# CAPACITOR_CHARGER.net
KiCad netlist of a schematic drawn in Altium Designer
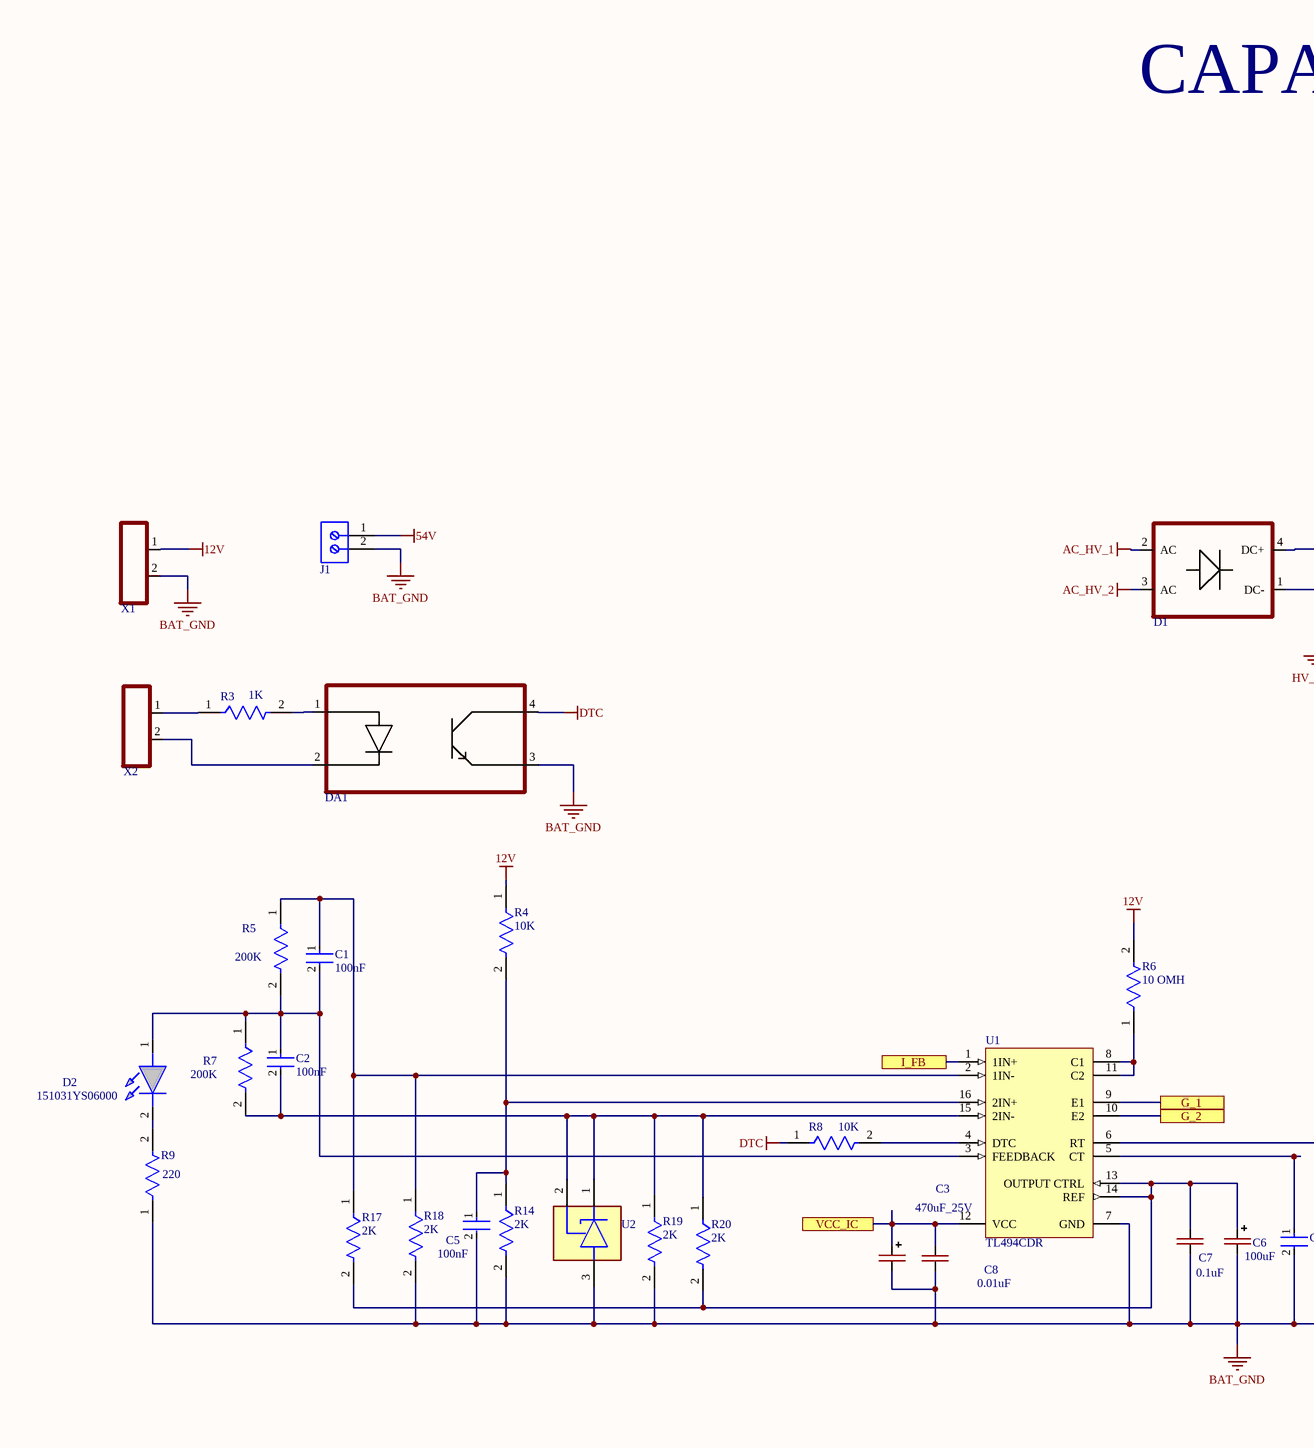
[diagram p0: CAPACITOR_CHARGER.SchDoc, left]
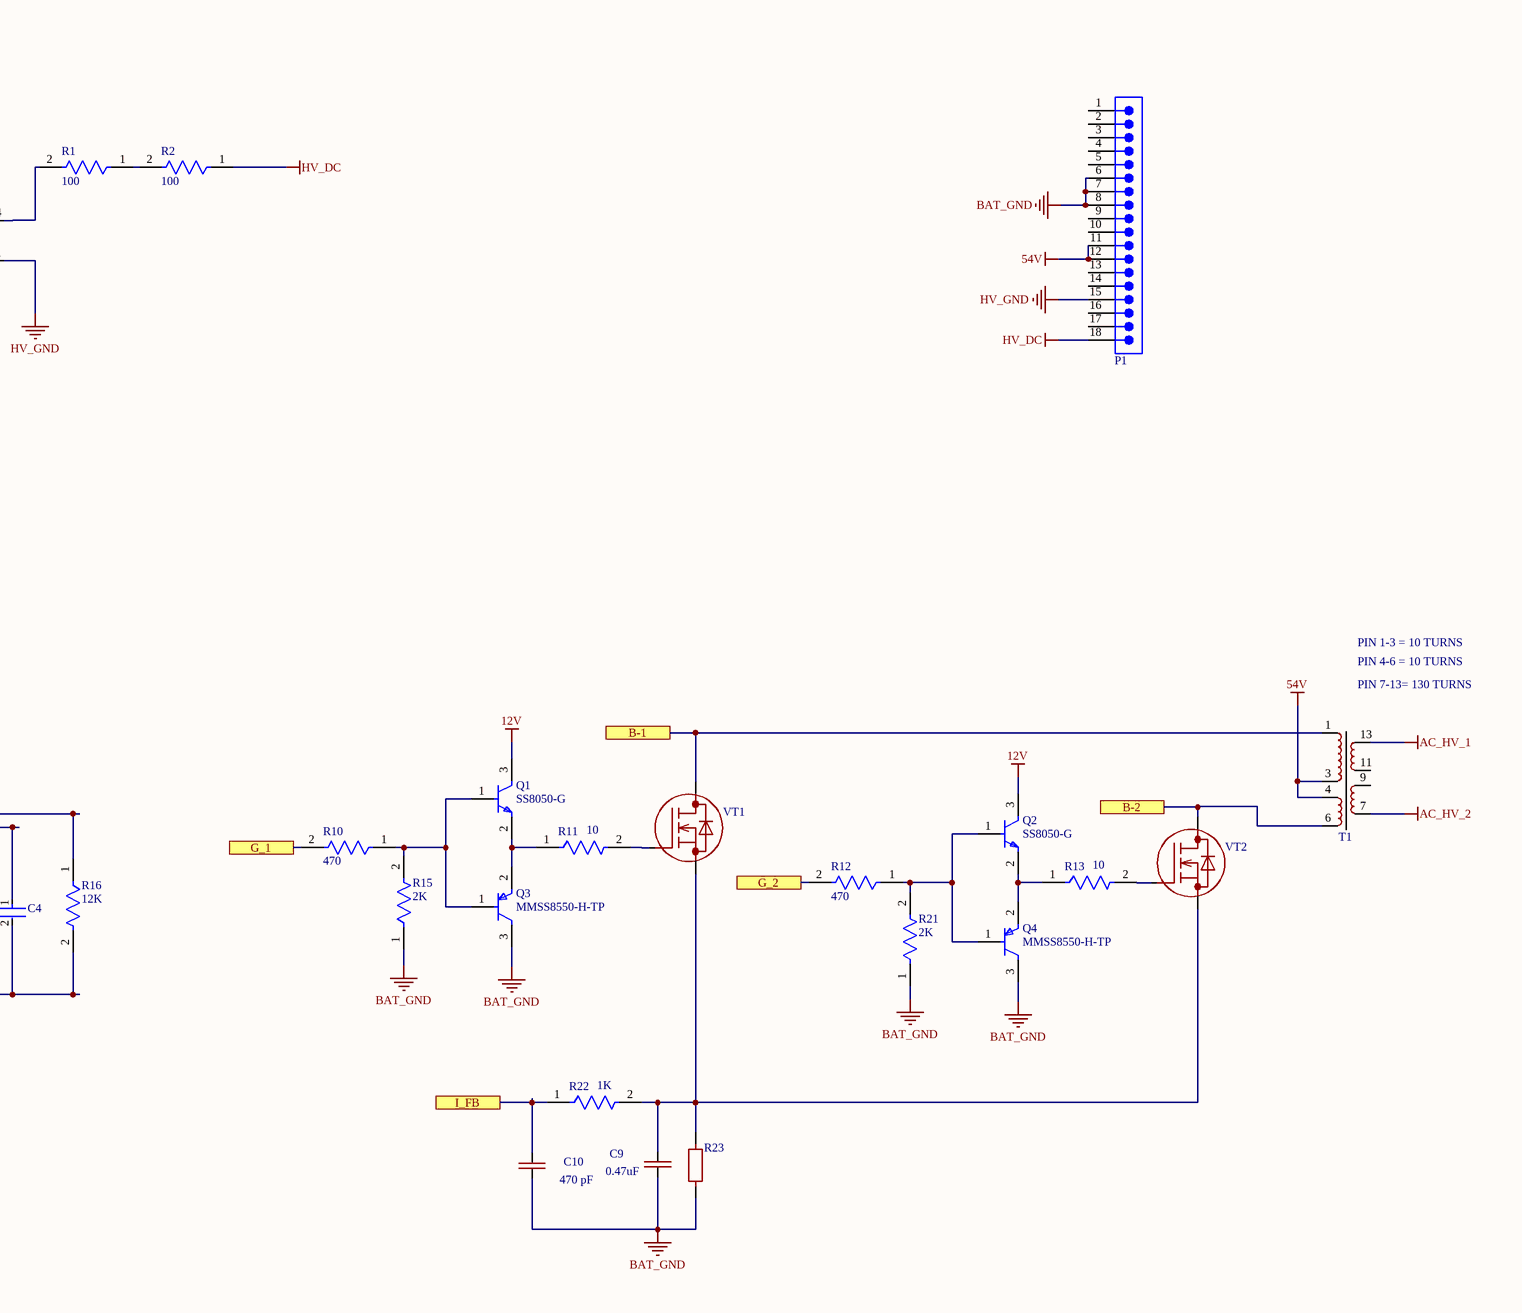
[diagram p1: CAPACITOR_CHARGER.SchDoc, right]

(export (version "E")
  (design (tool "Eeschema 10.0.6"))
  (components
    (comp (ref "C1")
      (value "100nF")
      (footprint "FP-C0805C-DN-MFG")
      (description "CAP CER 10000PF 50V X7R 0805")
      (fields
        (field (name "MANUFACTURER PART NUMBER") "C0805C103J5RACTU")
        (field (name "MANUFACTURER") "KEMET")
      )
      (libsource (lib "Altium Content Vault") (part "b4654b650e69147ec39a6b967a45e02"))
    )
    (comp (ref "C2")
      (value "100nF")
      (footprint "FP-C0805C-DN-MFG")
      (description "CAP CER 10000PF 50V X7R 0805")
      (fields
        (field (name "MANUFACTURER PART NUMBER") "C0805C103J5RACTU")
        (field (name "MANUFACTURER") "KEMET")
      )
      (libsource (lib "Altium Content Vault") (part "b4654b650e69147ec39a6b967a45e02"))
    )
    (comp (ref "C3")
      (value "470uF_25V")
      (footprint "CAP_SMD_Size_G")
      (libsource (lib "PASSIVE_COMPONENTS") (part "CAP-POLAR"))
    )
    (comp (ref "C4")
      (value "C0805C102K5RACTU")
      (footprint "FP-C0805C-DN-MFG")
      (description "CAP CER 1000PF 50V X7R 0805")
      (fields
        (field (name "OCTOPART") "https://octopart.com/c0805c102k5ractu-kemet-93010")
        (field (name "TOLERANCE") "0.1")
      )
      (libsource (lib "Altium Content Vault") (part "b4654b650e69147ec39a6b967a45e02"))
    )
    (comp (ref "C5")
      (value "100nF")
      (footprint "FP-C0805C-DN-MFG")
      (description "CAP CER 10000PF 50V X7R 0805")
      (fields
        (field (name "MANUFACTURER PART NUMBER") "C0805C103J5RACTU")
        (field (name "MANUFACTURER") "KEMET")
      )
      (libsource (lib "Altium Content Vault") (part "b4654b650e69147ec39a6b967a45e02"))
    )
    (comp (ref "C6")
      (value "100uF")
      (footprint "CAP-TAN-D")
      (libsource (lib "PASSIVE_COMPONENTS") (part "CAP-POLAR"))
    )
    (comp (ref "C7")
      (value "0.1uF")
      (footprint "CAP-0805")
      (libsource (lib "PASSIVE_COMPONENTS") (part "CAP-NON-POLAR"))
    )
    (comp (ref "C8")
      (value "0.01uF")
      (footprint "CAP-0805")
      (libsource (lib "PASSIVE_COMPONENTS") (part "CAP-NON-POLAR"))
    )
    (comp (ref "C9")
      (value "0.47uF")
      (footprint "CAP-0805")
      (libsource (lib "PASSIVE_COMPONENTS") (part "CAP-NON-POLAR"))
    )
    (comp (ref "C10")
      (value "470 pF")
      (footprint "CAP-0805")
      (libsource (lib "PASSIVE_COMPONENTS") (part "CAP-NON-POLAR"))
    )
    (comp (ref "D1") (value "RS40X") (footprint "RS40X") (libsource (lib "RS40X") (part "RS40X")))
    (comp (ref "D2")
      (value "151031YS06000")
      (footprint "LED_RED")
      (description "WURTH ELEKTRONIK - 151031YS06000 - LED, Yellow, Through Hole, T-1 (3mm), 30 mA, 2 V, 590 nm")
      (fields (field (name "MOUSER PART NUMBER") "710-151031YS06000"))
      (libsource (lib "Optic-LED") (part "LED"))
    )
    (comp (ref "DA1") (value "PC817") (footprint "4-SMD") (libsource (lib "PC817") (part "PC817")))
    (comp (ref "J1")
      (value "691101710002")
      (footprint "691101710002")
      (description "WR-TBL Series 101 Horizontal Entry Modular, THT, pitch 5mm, 2p")
      (fields (field (name "MANUFACTURER") "Wurth Elektronik"))
      (libsource (lib "Altium_WR-TBL (rev22b)") (part "691101710002"))
    )
    (comp (ref "P1")
      (value "61301811021")
      (footprint "61301811021")
      (description "WR-PHD Pin Header, THT, Angled, pitch 2.54mm, 1 Row, 18P")
      (fields (field (name "MANUFACTURER") "Wurth Elektronik"))
      (libsource (lib "Altium_WR-PHD (rev22b)") (part "61301811021"))
    )
    (comp (ref "Q1")
      (value "SS8050-G")
      (footprint "FP-SS8050-G-MFG")
      (description "NPN TRANSISTOR 1.5A 40V SOT-23 R")
      (libsource (lib "Altium Content Vault") (part "2a1388f82443b098dcd57d24ac7632d"))
    )
    (comp (ref "Q2")
      (value "SS8050-G")
      (footprint "FP-SS8050-G-MFG")
      (description "NPN TRANSISTOR 1.5A 40V SOT-23 R")
      (libsource (lib "Altium Content Vault") (part "2a1388f82443b098dcd57d24ac7632d"))
    )
    (comp (ref "Q3")
      (value "MMSS8550-H-TP")
      (footprint "FP-SOT-23-IPC_B")
      (description "TRANS PNP 25V 1.5A SOT23")
      (libsource (lib "Altium Content Vault") (part "0e8486ed3b47d9c69b8404ba87cf0f7"))
    )
    (comp (ref "Q4")
      (value "MMSS8550-H-TP")
      (footprint "FP-SOT-23-IPC_B")
      (description "TRANS PNP 25V 1.5A SOT23")
      (libsource (lib "Altium Content Vault") (part "0e8486ed3b47d9c69b8404ba87cf0f7"))
    )
    (comp (ref "R1")
      (value "100")
      (footprint "RES-2W")
      (libsource (lib "PASSIVE_COMPONENTS") (part "RES-CONST"))
    )
    (comp (ref "R2")
      (value "100")
      (footprint "RES-2W")
      (libsource (lib "PASSIVE_COMPONENTS") (part "RES-CONST"))
    )
    (comp (ref "R3")
      (value "1K")
      (footprint "RES-0805")
      (libsource (lib "PASSIVE_COMPONENTS") (part "RES-CONST"))
    )
    (comp (ref "R4")
      (value "10K")
      (footprint "FP-CRCW0805-e3-MFG")
      (description "RES Thick Film, 2kΩ, 1%, 0.125W, 100ppm/°C, 0805")
      (fields (field (name "TOLERANCE") "1%"))
      (libsource (lib "Pasive_components") (part "CMP-2001-04908-2"))
    )
    (comp (ref "R5")
      (value "200K")
      (footprint "FP-CRCW0805-e3-MFG")
      (description "RES Thick Film, 2kΩ, 1%, 0.125W, 100ppm/°C, 0805")
      (fields (field (name "TOLERANCE") "1%"))
      (libsource (lib "Pasive_components") (part "CMP-2001-04908-2"))
    )
    (comp (ref "R6")
      (value "10 OMH")
      (footprint "RES-1206")
      (libsource (lib "PASSIVE_COMPONENTS") (part "RES-CONST"))
    )
    (comp (ref "R7")
      (value "200K")
      (footprint "FP-CRCW0805-e3-MFG")
      (description "RES Thick Film, 2kΩ, 1%, 0.125W, 100ppm/°C, 0805")
      (fields (field (name "TOLERANCE") "1%"))
      (libsource (lib "Pasive_components") (part "CMP-2001-04908-2"))
    )
    (comp (ref "R8")
      (value "10K")
      (footprint "RES-0805")
      (libsource (lib "PASSIVE_COMPONENTS") (part "RES-CONST"))
    )
    (comp (ref "R9")
      (value "220")
      (footprint "RES-0805")
      (libsource (lib "PASSIVE_COMPONENTS") (part "RES-CONST"))
    )
    (comp (ref "R10")
      (value "470")
      (footprint "RES-0805")
      (libsource (lib "PASSIVE_COMPONENTS") (part "RES-CONST"))
    )
    (comp (ref "R11")
      (value "10")
      (footprint "RES-0805")
      (libsource (lib "PASSIVE_COMPONENTS") (part "RES-CONST"))
    )
    (comp (ref "R12")
      (value "470")
      (footprint "RES-0805")
      (libsource (lib "PASSIVE_COMPONENTS") (part "RES-CONST"))
    )
    (comp (ref "R13")
      (value "10")
      (footprint "RES-0805")
      (libsource (lib "PASSIVE_COMPONENTS") (part "RES-CONST"))
    )
    (comp (ref "R14")
      (value "2K")
      (footprint "FP-CRCW0805-e3-MFG")
      (description "RES Thick Film, 2kΩ, 1%, 0.125W, 100ppm/°C, 0805")
      (fields (field (name "TOLERANCE") "1%"))
      (libsource (lib "Pasive_components") (part "CMP-2001-04908-2"))
    )
    (comp (ref "R15")
      (value "2K")
      (footprint "RES-0805")
      (libsource (lib "PASSIVE_COMPONENTS") (part "RES-CONST"))
    )
    (comp (ref "R16")
      (value "12K")
      (footprint "FP-CRCW0805-e3-MFG")
      (description "RES Thick Film, 12kΩ, 1%, 0.125W, 100ppm/°C, 0805")
      (fields (field (name "TOLERANCE") "1%"))
      (libsource (lib "Pasive_components") (part "CMP-2001-04908-2"))
    )
    (comp (ref "R17")
      (value "2K")
      (footprint "FP-CRCW0805-e3-MFG")
      (description "RES Thick Film, 2kΩ, 1%, 0.125W, 100ppm/°C, 0805")
      (fields (field (name "TOLERANCE") "1%"))
      (libsource (lib "Pasive_components") (part "CMP-2001-04908-2"))
    )
    (comp (ref "R18")
      (value "2K")
      (footprint "FP-CRCW0805-e3-MFG")
      (description "RES Thick Film, 82kΩ, 1%, 0.125W, 100ppm/°C, 0805")
      (fields (field (name "TOLERANCE") "1%"))
      (libsource (lib "Pasive_components") (part "CMP-2001-04908-2"))
    )
    (comp (ref "R19")
      (value "2K")
      (footprint "FP-CRCW0805-e3-MFG")
      (description "RES Thick Film, 2kΩ, 1%, 0.125W, 100ppm/°C, 0805")
      (fields (field (name "TOLERANCE") "1%"))
      (libsource (lib "Pasive_components") (part "CMP-2001-04908-2"))
    )
    (comp (ref "R20")
      (value "2K")
      (footprint "FP-CRCW0805-e3-MFG")
      (description "RES Thick Film, 2kΩ, 1%, 0.125W, 100ppm/°C, 0805")
      (fields (field (name "TOLERANCE") "1%"))
      (libsource (lib "Pasive_components") (part "CMP-2001-04908-2"))
    )
    (comp (ref "R21")
      (value "2K")
      (footprint "RES-0805")
      (libsource (lib "PASSIVE_COMPONENTS") (part "RES-CONST"))
    )
    (comp (ref "R22")
      (value "1K")
      (footprint "RES-0805")
      (libsource (lib "PASSIVE_COMPONENTS") (part "RES-CONST"))
    )
    (comp (ref "R23") (value "~") (footprint "RES-2W") (libsource (lib "PAS_COMPONENTS") (part "RES-CONST")))
    (comp (ref "T1")
      (value "ETD29")
      (footprint "TRANS_ETD_29")
      (libsource (lib "ETD_29") (part "Trans_ETD59"))
    )
    (comp (ref "U1")
      (value "TL494CDR")
      (footprint "D0016A_N")
      (fields (field (name "MANUFACTURER") "Texas Instruments"))
      (libsource (lib "Altium Content Vault") (part "TI-494D16"))
    )
    (comp (ref "U2")
      (value "TL431")
      (footprint "TL431_SOT-23-3(A)")
      (description "TL431_SOT-23-3")
      (libsource (lib "Diodes") (part "TL431_SOT-23-3"))
    )
    (comp (ref "VT1")
      (value "MOSFET-N-GDS")
      (footprint "TO-220-3")
      (libsource (lib "TRANSISTORS") (part "MOSFET-N-GDS"))
    )
    (comp (ref "VT2")
      (value "MOSFET-N-GDS")
      (footprint "TO-220-3")
      (libsource (lib "TRANSISTORS") (part "MOSFET-N-GDS"))
    )
    (comp (ref "X1") (value "CONN-2-PIN") (footprint "XH2-") (libsource (lib "XH 2PIN") (part "CONN-2-PIN")))
    (comp (ref "X2") (value "CONN-2-PIN") (footprint "XH2-") (libsource (lib "XH 2PIN") (part "CONN-2-PIN")))
  )
  (nets
    (net (code "1") (name "/B-1") (class "Default")
      (node (ref "T1") (pin "1") (pinfunction "1_1") (pintype "passive"))
      (node (ref "VT1") (pin "2") (pinfunction "D_2") (pintype "passive"))
    )
    (net (code "2") (name "/B-2") (class "Default")
      (node (ref "T1") (pin "6") (pinfunction "6_6") (pintype "passive"))
      (node (ref "VT2") (pin "2") (pinfunction "D_2") (pintype "passive"))
    )
    (net (code "3") (name "/G_1") (class "Default")
      (node (ref "R10") (pin "2") (pinfunction "2_2") (pintype "passive"))
      (node (ref "U1") (pin "9") (pinfunction "E1_9") (pintype "passive"))
    )
    (net (code "4") (name "/G_2") (class "Default")
      (node (ref "R12") (pin "2") (pinfunction "2_2") (pintype "passive"))
      (node (ref "U1") (pin "10") (pinfunction "E2_10") (pintype "passive"))
    )
    (net (code "5") (name "/I_FB") (class "Default")
      (node (ref "C10") (pin "2") (pinfunction "2_2") (pintype "passive"))
      (node (ref "R22") (pin "1") (pinfunction "1_1") (pintype "passive"))
      (node (ref "U1") (pin "1") (pinfunction "1IN+_1") (pintype "input"))
    )
    (net (code "6") (name "/VCC_IC") (class "Default")
      (node (ref "C3") (pin "1") (pinfunction "+_1") (pintype "passive"))
      (node (ref "C8") (pin "2") (pinfunction "2_2") (pintype "passive"))
      (node (ref "U1") (pin "12") (pinfunction "VCC_12") (pintype "power_in"))
    )
    (net (code "7") (name "12V") (class "Default")
      (node (ref "Q1") (pin "3") (pinfunction "C_3") (pintype "passive"))
      (node (ref "Q2") (pin "3") (pinfunction "C_3") (pintype "passive"))
      (node (ref "R4") (pin "1") (pinfunction "1_1") (pintype "passive"))
      (node (ref "R6") (pin "2") (pinfunction "2_2") (pintype "passive"))
      (node (ref "X1") (pin "1") (pinfunction "1_1") (pintype "passive"))
    )
    (net (code "8") (name "54V") (class "Default")
      (node (ref "J1") (pin "1") (pinfunction "1_1") (pintype "passive"))
      (node (ref "P1") (pin "11") (pinfunction "11_11") (pintype "passive"))
      (node (ref "P1") (pin "12") (pinfunction "12_12") (pintype "passive"))
      (node (ref "T1") (pin "3") (pinfunction "3_3") (pintype "passive"))
      (node (ref "T1") (pin "4") (pinfunction "4_4") (pintype "passive"))
    )
    (net (code "9") (name "AC_HV_1") (class "Default")
      (node (ref "D1") (pin "2") (pinfunction "AC_2") (pintype "passive"))
      (node (ref "T1") (pin "13") (pinfunction "13_13") (pintype "passive"))
    )
    (net (code "10") (name "AC_HV_2") (class "Default")
      (node (ref "D1") (pin "3") (pinfunction "AC_3") (pintype "passive"))
      (node (ref "T1") (pin "7") (pinfunction "7_7") (pintype "passive"))
    )
    (net (code "11") (name "BAT_GND") (class "Default")
      (node (ref "C10") (pin "1") (pinfunction "1_1") (pintype "passive"))
      (node (ref "C3") (pin "2") (pinfunction "-_2") (pintype "passive"))
      (node (ref "C4") (pin "2") (pinfunction "2_2") (pintype "passive"))
      (node (ref "C5") (pin "2") (pinfunction "2_2") (pintype "passive"))
      (node (ref "C6") (pin "2") (pinfunction "-_2") (pintype "passive"))
      (node (ref "C7") (pin "1") (pinfunction "1_1") (pintype "passive"))
      (node (ref "C8") (pin "1") (pinfunction "1_1") (pintype "passive"))
      (node (ref "C9") (pin "1") (pinfunction "1_1") (pintype "passive"))
      (node (ref "DA1") (pin "3") (pinfunction "EMITTER_3") (pintype "passive"))
      (node (ref "J1") (pin "2") (pinfunction "2_2") (pintype "passive"))
      (node (ref "P1") (pin "6") (pinfunction "6_6") (pintype "passive"))
      (node (ref "P1") (pin "7") (pinfunction "7_7") (pintype "passive"))
      (node (ref "P1") (pin "8") (pinfunction "8_8") (pintype "passive"))
      (node (ref "Q3") (pin "3") (pinfunction "C_3") (pintype "passive"))
      (node (ref "Q4") (pin "3") (pinfunction "C_3") (pintype "passive"))
      (node (ref "R14") (pin "2") (pinfunction "2_2") (pintype "passive"))
      (node (ref "R15") (pin "1") (pinfunction "1_1") (pintype "passive"))
      (node (ref "R16") (pin "2") (pinfunction "2_2") (pintype "passive"))
      (node (ref "R18") (pin "2") (pinfunction "2_2") (pintype "passive"))
      (node (ref "R19") (pin "2") (pinfunction "2_2") (pintype "passive"))
      (node (ref "R21") (pin "1") (pinfunction "1_1") (pintype "passive"))
      (node (ref "R23") (pin "1") (pinfunction "1_1") (pintype "passive"))
      (node (ref "R9") (pin "1") (pinfunction "1_1") (pintype "passive"))
      (node (ref "U1") (pin "7") (pinfunction "GND_7") (pintype "power_in"))
      (node (ref "U2") (pin "3") (pinfunction "A_3") (pintype "passive"))
      (node (ref "X1") (pin "2") (pinfunction "2_2") (pintype "passive"))
    )
    (net (code "12") (name "DTC") (class "Default")
      (node (ref "DA1") (pin "4") (pinfunction "COLLECTOR_4") (pintype "passive"))
      (node (ref "R8") (pin "1") (pinfunction "1_1") (pintype "passive"))
    )
    (net (code "13") (name "HV_DC") (class "Default")
      (node (ref "P1") (pin "18") (pinfunction "18_18") (pintype "passive"))
      (node (ref "R2") (pin "1") (pinfunction "1_1") (pintype "passive"))
    )
    (net (code "14") (name "HV_GND") (class "Default")
      (node (ref "D1") (pin "1") (pinfunction "DC-_1") (pintype "passive"))
      (node (ref "P1") (pin "15") (pinfunction "15_15") (pintype "passive"))
    )
    (net (code "15") (name "Net-(C6-+)") (class "Default")
      (node (ref "C6") (pin "1") (pinfunction "+_1") (pintype "passive"))
      (node (ref "C7") (pin "2") (pinfunction "2_2") (pintype "passive"))
      (node (ref "R17") (pin "2") (pinfunction "2_2") (pintype "passive"))
      (node (ref "R20") (pin "2") (pinfunction "2_2") (pintype "passive"))
      (node (ref "U1") (pin "13") (pinfunction "OUTPUT_CTRL_13") (pintype "input"))
      (node (ref "U1") (pin "14") (pinfunction "REF_14") (pintype "output"))
    )
    (net (code "16") (name "Net-(D1-DC+)") (class "Default")
      (node (ref "D1") (pin "4") (pinfunction "DC+_4") (pintype "passive"))
      (node (ref "R1") (pin "2") (pinfunction "2_2") (pintype "passive"))
    )
    (net (code "17") (name "Net-(D2-A)") (class "Default")
      (node (ref "C1") (pin "2") (pinfunction "2_2") (pintype "passive"))
      (node (ref "C2") (pin "1") (pinfunction "1_1") (pintype "passive"))
      (node (ref "D2") (pin "1") (pinfunction "A_1") (pintype "passive"))
      (node (ref "R5") (pin "2") (pinfunction "2_2") (pintype "passive"))
      (node (ref "R7") (pin "1") (pinfunction "1_1") (pintype "passive"))
      (node (ref "U1") (pin "3") (pinfunction "FEEDBACK_3") (pintype "input"))
    )
    (net (code "18") (name "Net-(D2-K)") (class "Default")
      (node (ref "D2") (pin "2") (pinfunction "K_2") (pintype "passive"))
      (node (ref "R9") (pin "2") (pinfunction "2_2") (pintype "passive"))
    )
    (net (code "19") (name "Net-(DA1-ANODE)") (class "Default")
      (node (ref "DA1") (pin "1") (pinfunction "ANODE_1") (pintype "passive"))
      (node (ref "R3") (pin "2") (pinfunction "2_2") (pintype "passive"))
    )
    (net (code "20") (name "Net-(DA1-CATHODE)") (class "Default")
      (node (ref "DA1") (pin "2") (pinfunction "CATHODE_2") (pintype "passive"))
      (node (ref "X2") (pin "2") (pinfunction "2_2") (pintype "passive"))
    )
    (net (code "21") (name "Net-(Q1-B)") (class "Default")
      (node (ref "Q1") (pin "1") (pinfunction "B_1") (pintype "passive"))
      (node (ref "Q3") (pin "1") (pinfunction "B_1") (pintype "passive"))
      (node (ref "R10") (pin "1") (pinfunction "1_1") (pintype "passive"))
      (node (ref "R15") (pin "2") (pinfunction "2_2") (pintype "passive"))
    )
    (net (code "22") (name "Net-(Q1-E)") (class "Default")
      (node (ref "Q1") (pin "2") (pinfunction "E_2") (pintype "passive"))
      (node (ref "Q3") (pin "2") (pinfunction "E_2") (pintype "passive"))
      (node (ref "R11") (pin "1") (pinfunction "1_1") (pintype "passive"))
    )
    (net (code "23") (name "Net-(Q2-B)") (class "Default")
      (node (ref "Q2") (pin "1") (pinfunction "B_1") (pintype "passive"))
      (node (ref "Q4") (pin "1") (pinfunction "B_1") (pintype "passive"))
      (node (ref "R12") (pin "1") (pinfunction "1_1") (pintype "passive"))
      (node (ref "R21") (pin "2") (pinfunction "2_2") (pintype "passive"))
    )
    (net (code "24") (name "Net-(Q2-E)") (class "Default")
      (node (ref "Q2") (pin "2") (pinfunction "E_2") (pintype "passive"))
      (node (ref "Q4") (pin "2") (pinfunction "E_2") (pintype "passive"))
      (node (ref "R13") (pin "1") (pinfunction "1_1") (pintype "passive"))
    )
    (net (code "25") (name "Net-(R1-Pad1)") (class "Default")
      (node (ref "R1") (pin "1") (pinfunction "1_1") (pintype "passive"))
      (node (ref "R2") (pin "2") (pinfunction "2_2") (pintype "passive"))
    )
    (net (code "26") (name "Net-(R3-Pad1)") (class "Default")
      (node (ref "R3") (pin "1") (pinfunction "1_1") (pintype "passive"))
      (node (ref "X2") (pin "1") (pinfunction "1_1") (pintype "passive"))
    )
    (net (code "27") (name "Net-(U1-1IN-)") (class "Default")
      (node (ref "C1") (pin "1") (pinfunction "1_1") (pintype "passive"))
      (node (ref "R17") (pin "1") (pinfunction "1_1") (pintype "passive"))
      (node (ref "R18") (pin "1") (pinfunction "1_1") (pintype "passive"))
      (node (ref "R5") (pin "1") (pinfunction "1_1") (pintype "passive"))
      (node (ref "U1") (pin "2") (pinfunction "1IN-_2") (pintype "input"))
    )
    (net (code "28") (name "Net-(U1-2IN+)") (class "Default")
      (node (ref "C5") (pin "1") (pinfunction "1_1") (pintype "passive"))
      (node (ref "R14") (pin "1") (pinfunction "1_1") (pintype "passive"))
      (node (ref "R4") (pin "2") (pinfunction "2_2") (pintype "passive"))
      (node (ref "U1") (pin "16") (pinfunction "2IN+_16") (pintype "input"))
    )
    (net (code "29") (name "Net-(U1-2IN-)") (class "Default")
      (node (ref "C2") (pin "2") (pinfunction "2_2") (pintype "passive"))
      (node (ref "R19") (pin "1") (pinfunction "1_1") (pintype "passive"))
      (node (ref "R20") (pin "1") (pinfunction "1_1") (pintype "passive"))
      (node (ref "R7") (pin "2") (pinfunction "2_2") (pintype "passive"))
      (node (ref "U1") (pin "15") (pinfunction "2IN-_15") (pintype "input"))
      (node (ref "U2") (pin "1") (pinfunction "C_1") (pintype "passive"))
      (node (ref "U2") (pin "2") (pinfunction "REF_2") (pintype "passive"))
    )
    (net (code "30") (name "Net-(U1-C1)") (class "Default")
      (node (ref "R6") (pin "1") (pinfunction "1_1") (pintype "passive"))
      (node (ref "U1") (pin "11") (pinfunction "C2_11") (pintype "passive"))
      (node (ref "U1") (pin "8") (pinfunction "C1_8") (pintype "passive"))
    )
    (net (code "31") (name "Net-(U1-CT)") (class "Default")
      (node (ref "C4") (pin "1") (pinfunction "1_1") (pintype "passive"))
      (node (ref "U1") (pin "5") (pinfunction "CT_5") (pintype "passive"))
    )
    (net (code "32") (name "Net-(U1-DTC)") (class "Default")
      (node (ref "R8") (pin "2") (pinfunction "2_2") (pintype "passive"))
      (node (ref "U1") (pin "4") (pinfunction "DTC_4") (pintype "input"))
    )
    (net (code "33") (name "Net-(U1-RT)") (class "Default")
      (node (ref "R16") (pin "1") (pinfunction "1_1") (pintype "passive"))
      (node (ref "U1") (pin "6") (pinfunction "RT_6") (pintype "passive"))
    )
    (net (code "34") (name "Net-(VT1-G)") (class "Default")
      (node (ref "R11") (pin "2") (pinfunction "2_2") (pintype "passive"))
      (node (ref "VT1") (pin "1") (pinfunction "G_1") (pintype "passive"))
    )
    (net (code "35") (name "Net-(VT1-S)") (class "Default")
      (node (ref "C9") (pin "2") (pinfunction "2_2") (pintype "passive"))
      (node (ref "R22") (pin "2") (pinfunction "2_2") (pintype "passive"))
      (node (ref "R23") (pin "2") (pinfunction "2_2") (pintype "passive"))
      (node (ref "VT1") (pin "3") (pinfunction "S_3") (pintype "passive"))
      (node (ref "VT2") (pin "3") (pinfunction "S_3") (pintype "passive"))
    )
    (net (code "36") (name "Net-(VT2-G)") (class "Default")
      (node (ref "R13") (pin "2") (pinfunction "2_2") (pintype "passive"))
      (node (ref "VT2") (pin "1") (pinfunction "G_1") (pintype "passive"))
    )
    (net (code "37") (name "unconnected-(P1-Pad1)") (class "Default")
      (node (ref "P1") (pin "1") (pinfunction "1_1") (pintype "passive"))
    )
    (net (code "38") (name "unconnected-(P1-Pad2)") (class "Default")
      (node (ref "P1") (pin "2") (pinfunction "2_2") (pintype "passive"))
    )
    (net (code "39") (name "unconnected-(P1-Pad3)") (class "Default")
      (node (ref "P1") (pin "3") (pinfunction "3_3") (pintype "passive"))
    )
    (net (code "40") (name "unconnected-(P1-Pad4)") (class "Default")
      (node (ref "P1") (pin "4") (pinfunction "4_4") (pintype "passive"))
    )
    (net (code "41") (name "unconnected-(P1-Pad5)") (class "Default")
      (node (ref "P1") (pin "5") (pinfunction "5_5") (pintype "passive"))
    )
    (net (code "42") (name "unconnected-(P1-Pad9)") (class "Default")
      (node (ref "P1") (pin "9") (pinfunction "9_9") (pintype "passive"))
    )
    (net (code "43") (name "unconnected-(P1-Pad10)") (class "Default")
      (node (ref "P1") (pin "10") (pinfunction "10_10") (pintype "passive"))
    )
    (net (code "44") (name "unconnected-(P1-Pad13)") (class "Default")
      (node (ref "P1") (pin "13") (pinfunction "13_13") (pintype "passive"))
    )
    (net (code "45") (name "unconnected-(P1-Pad14)") (class "Default")
      (node (ref "P1") (pin "14") (pinfunction "14_14") (pintype "passive"))
    )
    (net (code "46") (name "unconnected-(P1-Pad16)") (class "Default")
      (node (ref "P1") (pin "16") (pinfunction "16_16") (pintype "passive"))
    )
    (net (code "47") (name "unconnected-(P1-Pad17)") (class "Default")
      (node (ref "P1") (pin "17") (pinfunction "17_17") (pintype "passive"))
    )
    (net (code "48") (name "unconnected-(T1-Pad9)") (class "Default")
      (node (ref "T1") (pin "9") (pinfunction "9_9") (pintype "passive"))
    )
    (net (code "49") (name "unconnected-(T1-Pad11)") (class "Default")
      (node (ref "T1") (pin "11") (pinfunction "11_11") (pintype "passive"))
    )
  )
)
